# SlaveOutput.net
KiCad netlist of a schematic drawn in EAGLE
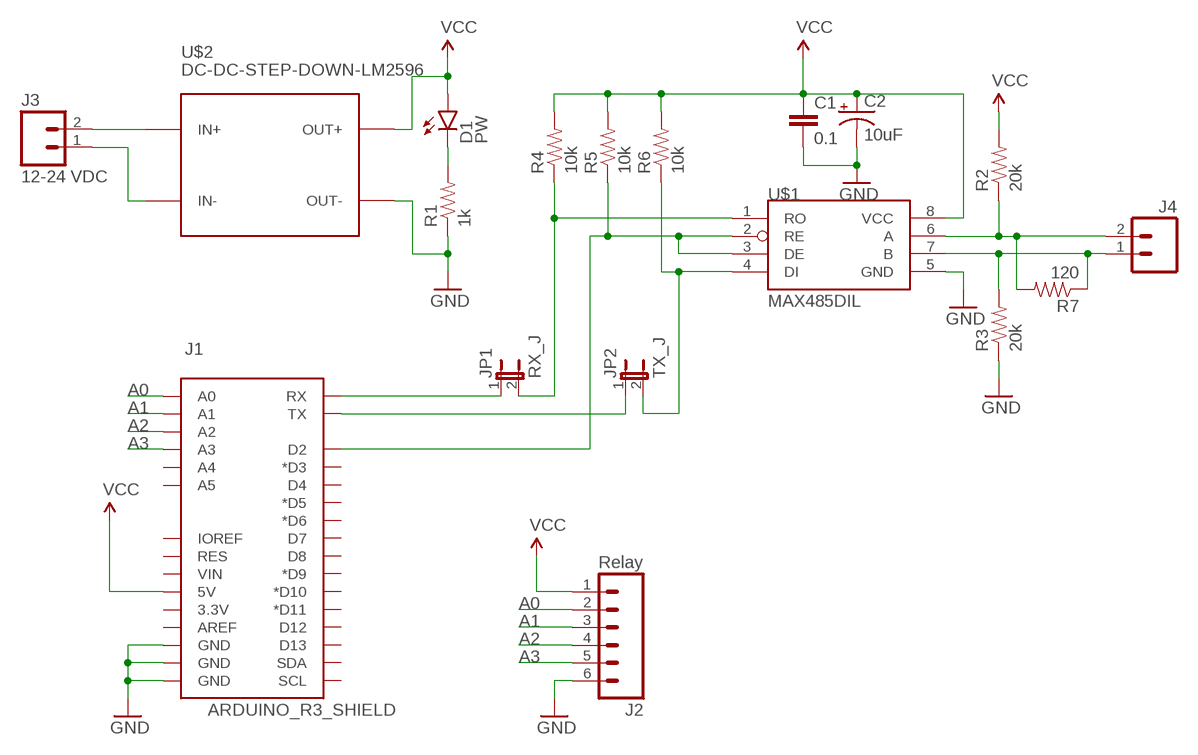
[diagram p0: schematic, sheet 1]

(export (version "E")
  (design (tool "Eeschema 10.0.6"))
  (components
    (comp (ref "C1")
      (value "0.1")
      (footprint "eagle-import:CAP-PTH-5MM")
      (libsource (lib "eagle-import") (part "CAPPTH1"))
    )
    (comp (ref "C2")
      (value "10uF")
      (footprint "eagle-import:CPOL-RADIAL-10UF-25V")
      (libsource (lib "eagle-import") (part "CAP_POLPTH2"))
    )
    (comp (ref "D1")
      (value "PW")
      (footprint "eagle-import:LED3MM")
      (libsource (lib "eagle-import") (part "LED3MM"))
    )
    (comp (ref "J1")
      (value "ARDUINO_R3_SHIELD")
      (footprint "eagle-import:UNO_R3_SHIELD")
      (libsource (lib "eagle-import") (part "ARDUINO_R3_SHIELD"))
    )
    (comp (ref "J2")
      (value "Relay")
      (footprint "eagle-import:1X06")
      (libsource (lib "eagle-import") (part "M06SILK_FEMALE_PTH"))
    )
    (comp (ref "J3")
      (value "12-24 VDC")
      (footprint "eagle-import:SCREWTERMINAL-5MM-2")
      (libsource (lib "eagle-import") (part "M025MM"))
    )
    (comp (ref "J4")
      (value "M025MM")
      (footprint "eagle-import:SCREWTERMINAL-5MM-2")
      (libsource (lib "eagle-import") (part "M025MM"))
    )
    (comp (ref "JP1")
      (value "RX_J")
      (footprint "eagle-import:1X02")
      (libsource (lib "eagle-import") (part "JUMPER-2PTH"))
    )
    (comp (ref "JP2")
      (value "TX_J")
      (footprint "eagle-import:1X02")
      (libsource (lib "eagle-import") (part "JUMPER-2PTH"))
    )
    (comp (ref "R1")
      (value "1k")
      (footprint "eagle-import:AXIAL-0.3")
      (libsource (lib "eagle-import") (part "RESISTORAXIAL-0.3"))
    )
    (comp (ref "R2")
      (value "20k")
      (footprint "eagle-import:AXIAL-0.3")
      (libsource (lib "eagle-import") (part "RESISTORAXIAL-0.3"))
    )
    (comp (ref "R3")
      (value "20k")
      (footprint "eagle-import:AXIAL-0.3")
      (libsource (lib "eagle-import") (part "RESISTORAXIAL-0.3"))
    )
    (comp (ref "R4")
      (value "10k")
      (footprint "eagle-import:AXIAL-0.3")
      (libsource (lib "eagle-import") (part "RESISTORAXIAL-0.3"))
    )
    (comp (ref "R5")
      (value "10k")
      (footprint "eagle-import:AXIAL-0.3")
      (libsource (lib "eagle-import") (part "RESISTORAXIAL-0.3"))
    )
    (comp (ref "R6")
      (value "10k")
      (footprint "eagle-import:AXIAL-0.3")
      (libsource (lib "eagle-import") (part "RESISTORAXIAL-0.3"))
    )
    (comp (ref "R7")
      (value "120")
      (footprint "eagle-import:AXIAL-0.3")
      (libsource (lib "eagle-import") (part "RESISTORAXIAL-0.3"))
    )
    (comp (ref "U$1")
      (value "MAX485DIL")
      (footprint "eagle-import:DIL08")
      (libsource (lib "eagle-import") (part "MAX485DIL"))
    )
    (comp (ref "U$2")
      (value "DC-DC-STEP-DOWN-LM2596")
      (footprint "eagle-import:DC-DC-STEP-DOWN-LM2596")
      (libsource (lib "eagle-import") (part "DC-DC-STEP-DOWN-LM2596"))
    )
  )
  (nets
    (net (code "1") (name "/A0") (class "Default")
      (node (ref "J1") (pin "A0") (pinfunction "A0_A0") (pintype "bidirectional"))
      (node (ref "J2") (pin "2") (pinfunction "2_2") (pintype "passive"))
    )
    (net (code "2") (name "/A1") (class "Default")
      (node (ref "J1") (pin "A1") (pinfunction "A1_A1") (pintype "bidirectional"))
      (node (ref "J2") (pin "3") (pinfunction "3_3") (pintype "passive"))
    )
    (net (code "3") (name "/A2") (class "Default")
      (node (ref "J1") (pin "A2") (pinfunction "A2_A2") (pintype "bidirectional"))
      (node (ref "J2") (pin "4") (pinfunction "4_4") (pintype "passive"))
    )
    (net (code "4") (name "/A3") (class "Default")
      (node (ref "J1") (pin "A3") (pinfunction "A3_A3") (pintype "bidirectional"))
      (node (ref "J2") (pin "5") (pinfunction "5_5") (pintype "passive"))
    )
    (net (code "5") (name "GND") (class "Default")
      (node (ref "C1") (pin "2") (pinfunction "2_2") (pintype "passive"))
      (node (ref "C2") (pin "2") (pinfunction "-_2") (pintype "passive"))
      (node (ref "J1") (pin "GND@0") (pinfunction "GND_GND@0") (pintype "bidirectional"))
      (node (ref "J1") (pin "GND@1") (pinfunction "GND_GND@1") (pintype "bidirectional"))
      (node (ref "J1") (pin "GND@2") (pinfunction "GND_GND@2") (pintype "bidirectional"))
      (node (ref "J2") (pin "6") (pinfunction "6_6") (pintype "passive"))
      (node (ref "R1") (pin "P$1") (pinfunction "1_P$1") (pintype "passive"))
      (node (ref "R3") (pin "P$1") (pinfunction "1_P$1") (pintype "passive"))
      (node (ref "U$1") (pin "5") (pinfunction "GND_5") (pintype "bidirectional"))
      (node (ref "U$2") (pin "OUT-") (pinfunction "OUT-_OUT-") (pintype "bidirectional"))
    )
    (net (code "6") (name "Net-(D1-C)") (class "Default")
      (node (ref "D1") (pin "K") (pinfunction "C_K") (pintype "passive"))
      (node (ref "R1") (pin "P$2") (pinfunction "2_P$2") (pintype "passive"))
    )
    (net (code "7") (name "Net-(J1-PadRX)") (class "Default")
      (node (ref "J1") (pin "RX") (pinfunction "RX_RX") (pintype "bidirectional"))
      (node (ref "JP1") (pin "1") (pinfunction "1_1") (pintype "passive"))
    )
    (net (code "8") (name "Net-(J1-PadTX)") (class "Default")
      (node (ref "J1") (pin "TX") (pinfunction "TX_TX") (pintype "bidirectional"))
      (node (ref "JP2") (pin "1") (pinfunction "1_1") (pintype "passive"))
    )
    (net (code "9") (name "Net-(J3-Pad1)") (class "Default")
      (node (ref "J3") (pin "1") (pinfunction "1_1") (pintype "passive"))
      (node (ref "U$2") (pin "IN-") (pinfunction "IN-_IN-") (pintype "bidirectional"))
    )
    (net (code "10") (name "Net-(J3-Pad2)") (class "Default")
      (node (ref "J3") (pin "2") (pinfunction "2_2") (pintype "passive"))
      (node (ref "U$2") (pin "IN+") (pinfunction "IN+_IN+") (pintype "bidirectional"))
    )
    (net (code "11") (name "Net-(R2-1)") (class "Default")
      (node (ref "J4") (pin "2") (pinfunction "2_2") (pintype "passive"))
      (node (ref "R2") (pin "P$1") (pinfunction "1_P$1") (pintype "passive"))
      (node (ref "R7") (pin "P$2") (pinfunction "2_P$2") (pintype "passive"))
      (node (ref "U$1") (pin "6") (pinfunction "A_6") (pintype "bidirectional"))
    )
    (net (code "12") (name "Net-(R3-2)") (class "Default")
      (node (ref "J4") (pin "1") (pinfunction "1_1") (pintype "passive"))
      (node (ref "R3") (pin "P$2") (pinfunction "2_P$2") (pintype "passive"))
      (node (ref "R7") (pin "P$1") (pinfunction "1_P$1") (pintype "passive"))
      (node (ref "U$1") (pin "7") (pinfunction "B_7") (pintype "bidirectional"))
    )
    (net (code "13") (name "Net-(R4-1)") (class "Default")
      (node (ref "JP1") (pin "2") (pinfunction "2_2") (pintype "passive"))
      (node (ref "R4") (pin "P$1") (pinfunction "1_P$1") (pintype "passive"))
      (node (ref "U$1") (pin "1") (pinfunction "RO_1") (pintype "bidirectional"))
    )
    (net (code "14") (name "Net-(R5-1)") (class "Default")
      (node (ref "J1") (pin "D2") (pinfunction "D2_D2") (pintype "bidirectional"))
      (node (ref "R5") (pin "P$1") (pinfunction "1_P$1") (pintype "passive"))
      (node (ref "U$1") (pin "2") (pinfunction "RE_2") (pintype "bidirectional"))
      (node (ref "U$1") (pin "3") (pinfunction "DE_3") (pintype "bidirectional"))
    )
    (net (code "15") (name "Net-(R6-1)") (class "Default")
      (node (ref "JP2") (pin "2") (pinfunction "2_2") (pintype "passive"))
      (node (ref "R6") (pin "P$1") (pinfunction "1_P$1") (pintype "passive"))
      (node (ref "U$1") (pin "4") (pinfunction "DI_4") (pintype "bidirectional"))
    )
    (net (code "16") (name "VCC") (class "Default")
      (node (ref "C1") (pin "1") (pinfunction "1_1") (pintype "passive"))
      (node (ref "C2") (pin "1") (pinfunction "+_1") (pintype "passive"))
      (node (ref "D1") (pin "A") (pinfunction "A_A") (pintype "passive"))
      (node (ref "J1") (pin "5V") (pinfunction "5V_5V") (pintype "bidirectional"))
      (node (ref "J2") (pin "1") (pinfunction "1_1") (pintype "passive"))
      (node (ref "R2") (pin "P$2") (pinfunction "2_P$2") (pintype "passive"))
      (node (ref "R4") (pin "P$2") (pinfunction "2_P$2") (pintype "passive"))
      (node (ref "R5") (pin "P$2") (pinfunction "2_P$2") (pintype "passive"))
      (node (ref "R6") (pin "P$2") (pinfunction "2_P$2") (pintype "passive"))
      (node (ref "U$1") (pin "8") (pinfunction "VCC_8") (pintype "bidirectional"))
      (node (ref "U$2") (pin "OUT+") (pinfunction "OUT+_OUT+") (pintype "bidirectional"))
    )
    (net (code "17") (name "unconnected-(J1-*D3-PadD3)") (class "Default")
      (node (ref "J1") (pin "D3") (pinfunction "*D3_D3") (pintype "bidirectional"))
    )
    (net (code "18") (name "unconnected-(J1-*D5-PadD5)") (class "Default")
      (node (ref "J1") (pin "D5") (pinfunction "*D5_D5") (pintype "bidirectional"))
    )
    (net (code "19") (name "unconnected-(J1-*D6-PadD6)") (class "Default")
      (node (ref "J1") (pin "D6") (pinfunction "*D6_D6") (pintype "bidirectional"))
    )
    (net (code "20") (name "unconnected-(J1-*D9-PadD9)") (class "Default")
      (node (ref "J1") (pin "D9") (pinfunction "*D9_D9") (pintype "bidirectional"))
    )
    (net (code "21") (name "unconnected-(J1-*D10-PadD10)") (class "Default")
      (node (ref "J1") (pin "D10") (pinfunction "*D10_D10") (pintype "bidirectional"))
    )
    (net (code "22") (name "unconnected-(J1-*D11-PadD11)") (class "Default")
      (node (ref "J1") (pin "D11") (pinfunction "*D11_D11") (pintype "bidirectional"))
    )
    (net (code "23") (name "unconnected-(J1-Pad3.3V)") (class "Default")
      (node (ref "J1") (pin "3.3V") (pinfunction "3.3V_3.3V") (pintype "bidirectional"))
    )
    (net (code "24") (name "unconnected-(J1-PadA4)") (class "Default")
      (node (ref "J1") (pin "A4") (pinfunction "A4_A4") (pintype "bidirectional"))
    )
    (net (code "25") (name "unconnected-(J1-PadA5)") (class "Default")
      (node (ref "J1") (pin "A5") (pinfunction "A5_A5") (pintype "bidirectional"))
    )
    (net (code "26") (name "unconnected-(J1-PadAREF)") (class "Default")
      (node (ref "J1") (pin "AREF") (pinfunction "AREF_AREF") (pintype "bidirectional"))
    )
    (net (code "27") (name "unconnected-(J1-PadD4)") (class "Default")
      (node (ref "J1") (pin "D4") (pinfunction "D4_D4") (pintype "bidirectional"))
    )
    (net (code "28") (name "unconnected-(J1-PadD7)") (class "Default")
      (node (ref "J1") (pin "D7") (pinfunction "D7_D7") (pintype "bidirectional"))
    )
    (net (code "29") (name "unconnected-(J1-PadD8)") (class "Default")
      (node (ref "J1") (pin "D8") (pinfunction "D8_D8") (pintype "bidirectional"))
    )
    (net (code "30") (name "unconnected-(J1-PadD12)") (class "Default")
      (node (ref "J1") (pin "D12") (pinfunction "D12_D12") (pintype "bidirectional"))
    )
    (net (code "31") (name "unconnected-(J1-PadD13)") (class "Default")
      (node (ref "J1") (pin "D13") (pinfunction "D13_D13") (pintype "bidirectional"))
    )
    (net (code "32") (name "unconnected-(J1-PadIOREF)") (class "Default")
      (node (ref "J1") (pin "IOREF") (pinfunction "IOREF_IOREF") (pintype "bidirectional"))
    )
    (net (code "33") (name "unconnected-(J1-PadRES)") (class "Default")
      (node (ref "J1") (pin "RES") (pinfunction "RES_RES") (pintype "bidirectional"))
    )
    (net (code "34") (name "unconnected-(J1-PadSCL)") (class "Default")
      (node (ref "J1") (pin "SCL") (pinfunction "SCL_SCL") (pintype "bidirectional"))
    )
    (net (code "35") (name "unconnected-(J1-PadSDA)") (class "Default")
      (node (ref "J1") (pin "SDA") (pinfunction "SDA_SDA") (pintype "bidirectional"))
    )
    (net (code "36") (name "unconnected-(J1-PadVIN)") (class "Default")
      (node (ref "J1") (pin "VIN") (pinfunction "VIN_VIN") (pintype "bidirectional"))
    )
  )
)
